# PSU.net
KiCad netlist of a schematic drawn in Altium Designer
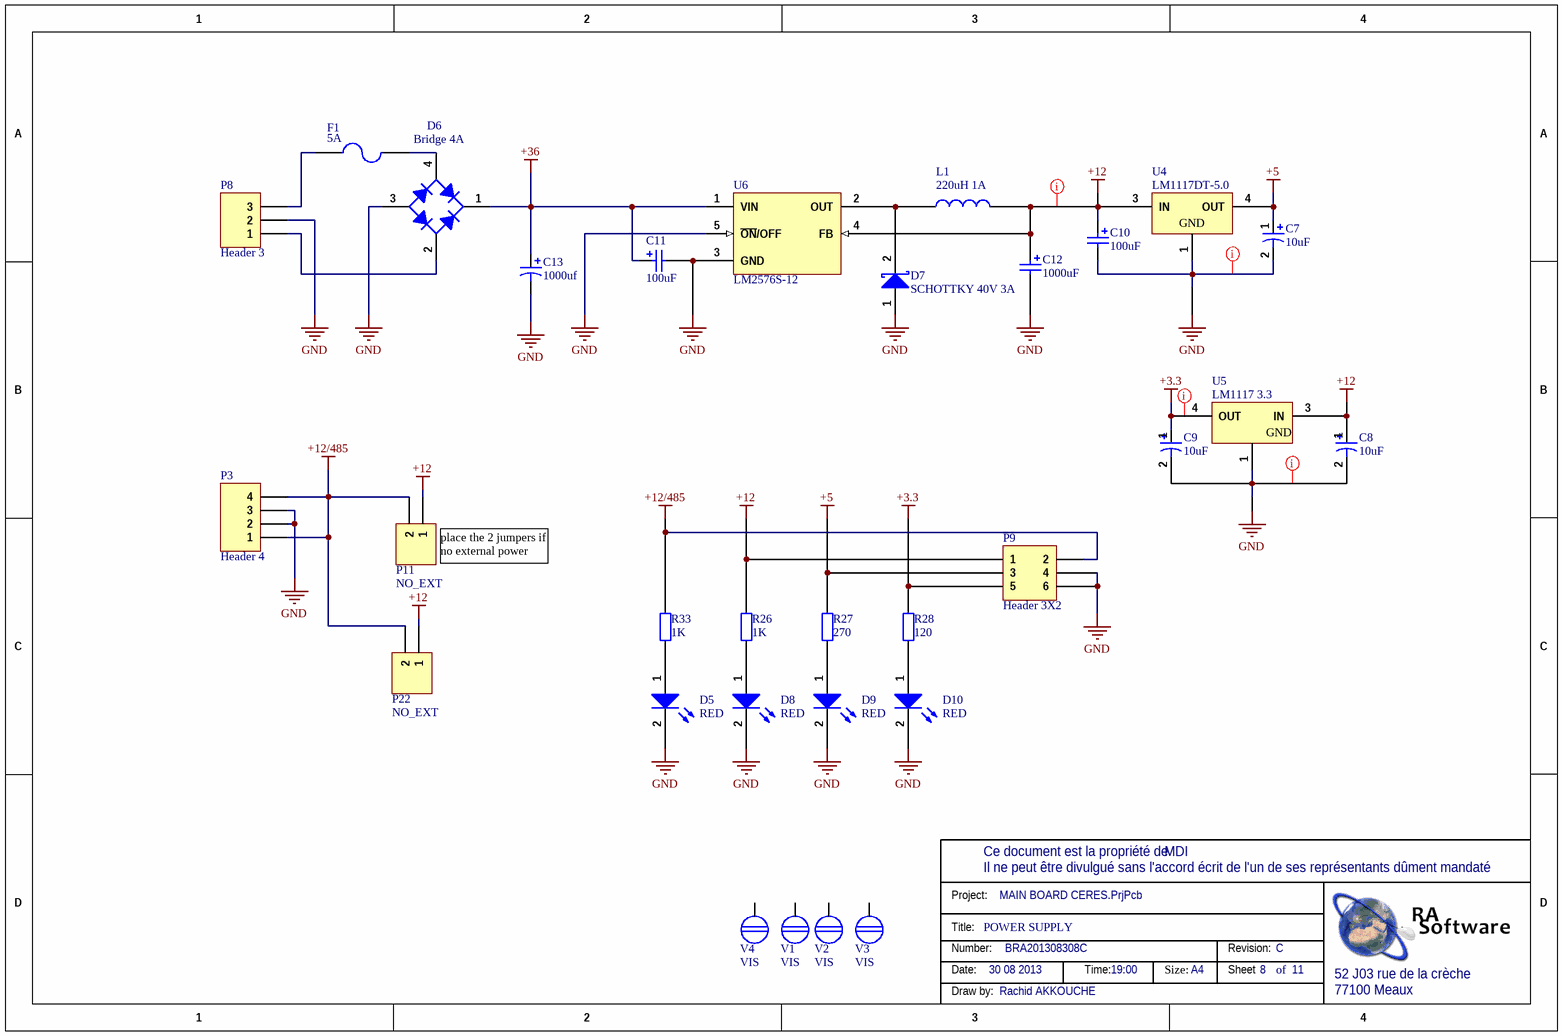
[diagram p0: PSU.SchDoc]

(export (version "E")
  (design (tool "Eeschema 10.0.6"))
  (components
    (comp (ref "C7")
      (value "10uF")
      (footprint "SYLANN:KEMET_4")
      (description "Polarized Capacitor")
      (fields
        (field (name "MANUFACTURER") "KEMET")
        (field (name "MANUFACTURER PART NUMBER") "EXV106M025A9BAA")
      )
      (libsource (lib "") (part "Cap Pol1_1"))
    )
    (comp (ref "C8")
      (value "10uF")
      (footprint "SYLANN:KEMET_4")
      (description "Polarized Capacitor")
      (fields
        (field (name "MANUFACTURER") "KEMET")
        (field (name "MANUFACTURER PART NUMBER") "EXV106M025A9BAA")
      )
      (libsource (lib "Miscellaneous Devices") (part "Cap Pol1"))
    )
    (comp (ref "C9")
      (value "10uF")
      (footprint "SYLANN:KEMET_4")
      (description "Polarized Capacitor")
      (fields
        (field (name "MANUFACTURER") "KEMET")
        (field (name "MANUFACTURER PART NUMBER") "EXV106M025A9BAA")
      )
      (libsource (lib "Miscellaneous Devices") (part "Cap Pol1"))
    )
    (comp (ref "C10")
      (value "100uF")
      (footprint "Kemet_63")
      (description "Polarized Capacitor")
      (fields
        (field (name "MANUFACTURER") "EPCOS")
        (field (name "MANUFACTURER PART NUMBER") "B41142A4107M")
        (field (name "HAUTEUR") "7.7")
        (field (name "LONGUEUR/HAUTEUR") "7.7")
      )
      (libsource (lib "BRA") (part "Cap Pol 100uF"))
    )
    (comp (ref "C11")
      (value "100uF")
      (footprint "Kemet_63")
      (description "Polarized Capacitor")
      (fields
        (field (name "MANUFACTURER") "EPCOS")
        (field (name "MANUFACTURER PART NUMBER") "B41142A4107M")
        (field (name "HAUTEUR") "7.7")
        (field (name "LONGUEUR/HAUTEUR") "7.7")
      )
      (libsource (lib "BRA") (part "Cap Pol 100uF"))
    )
    (comp (ref "C12")
      (value "1000uF")
      (footprint "KEMET_10")
      (description "Polarized Capacitor")
      (fields
        (field (name "MANUFACTURER") "PANASONIC")
        (field (name "MANUFACTURER PART NUMBER") "EEEFT1C102AP")
        (field (name "HAUTEUR") "10.2")
      )
      (libsource (lib "BRA") (part "Cap Pol 1000uF"))
    )
    (comp (ref "C13")
      (value "1000uf")
      (footprint "Capa Panasonic size J16")
      (description "Polarized Capacitor (Radial)")
      (fields
        (field (name "MANUFACTURER") "PANASONIC")
        (field (name "MANUFACTURER PART NUMBER") "EEVFK1H102M")
      )
      (libsource (lib "") (part "Cap Pol1_2"))
    )
    (comp (ref "D5")
      (value "HSMH-C190")
      (footprint "SYLANN:0603-LEDR")
      (description "Surface Mount Chip LED, Red")
      (fields
        (field (name "MANUFACTURER") "AVAGO TECHNOLOGIES")
        (field (name "MANUFACTURER PART NUMBER") "HSMH-C190.")
        (field (name "COULEUR") "RED")
        (field (name "LONGUEUR/HAUTEUR") "1.6")
      )
      (libsource (lib "Avago Optoelectronic LED") (part "HSMH-C190"))
    )
    (comp (ref "D6")
      (value "Bridge 4A")
      (footprint "Pont GBU")
      (description "Full Wave Diode Bridge")
      (fields
        (field (name "MANUFACTURER") "VISHAY GENERAL SEMICONDUCTOR")
        (field (name "MANUFACTURER PART NUMBER") "GBU6B-E3/45")
        (field (name "HAUTEUR") "18.8")
        (field (name "HAUTEUR CORPS MAX..") "18.8")
        (field (name "LONGUEUR/HAUTEUR") "18.8")
      )
      (libsource (lib "Miscellaneous Devices") (part "Bridge1"))
    )
    (comp (ref "D7")
      (value "SCHOTTKY 40V 3A")
      (footprint "DO220AA")
      (description "Schottky Diode")
      (fields
        (field (name "MANUFACTURER") "VISHAY")
        (field (name "MANUFACTURER PART NUMBER") "SS3P4-M3/84A")
        (field (name "PUBLISHER") "Altium Limited")
      )
      (libsource (lib "Miscellaneous Devices") (part "D Schottky"))
    )
    (comp (ref "D8")
      (value "HSMH-C190")
      (footprint "SYLANN:0603-LEDR")
      (description "Surface Mount Chip LED, Red")
      (fields
        (field (name "MANUFACTURER") "AVAGO TECHNOLOGIES")
        (field (name "MANUFACTURER PART NUMBER") "HSMH-C190.")
        (field (name "COULEUR") "RED")
        (field (name "LONGUEUR/HAUTEUR") "1.6")
      )
      (libsource (lib "Avago Optoelectronic LED") (part "HSMH-C190"))
    )
    (comp (ref "D9")
      (value "HSMH-C190")
      (footprint "SYLANN:0603-LEDR")
      (description "Surface Mount Chip LED, Red")
      (fields
        (field (name "MANUFACTURER") "AVAGO TECHNOLOGIES")
        (field (name "MANUFACTURER PART NUMBER") "HSMH-C190.")
        (field (name "COULEUR") "RED")
        (field (name "LONGUEUR/HAUTEUR") "1.6")
      )
      (libsource (lib "Avago Optoelectronic LED") (part "HSMH-C190"))
    )
    (comp (ref "D10")
      (value "HSMH-C190")
      (footprint "SYLANN:0603-LEDR")
      (description "Surface Mount Chip LED, Red")
      (fields
        (field (name "MANUFACTURER") "AVAGO TECHNOLOGIES")
        (field (name "MANUFACTURER PART NUMBER") "HSMH-C190.")
        (field (name "COULEUR") "RED")
        (field (name "LONGUEUR/HAUTEUR") "1.6")
      )
      (libsource (lib "Avago Optoelectronic LED") (part "HSMH-C190"))
    )
    (comp (ref "F1")
      (value "5A")
      (footprint "FUS5X20")
      (description "Fuse")
      (fields
        (field (name "MANUFACTURER") "KEYSTONE")
        (field (name "MANUFACTURER PART NUMBER") "4527")
        (field (name "PUBLISHER") "Altium Limited")
      )
      (libsource (lib "Miscellaneous Devices") (part "Fuse 2"))
    )
    (comp (ref "L1")
      (value "220uH 1A")
      (footprint "IND-1422435C")
      (description "Inductor")
      (fields
        (field (name "MANUFACTURER") "MULTICOMP")
        (field (name "MANUFACTURER PART NUMBER") "MCBFS7330-221MU")
        (field (name "LONGUEUR/HAUTEUR") "18.54")
      )
      (libsource (lib "Miscellaneous Devices") (part "Inductor"))
    )
    (comp (ref "P3")
      (value "Header 4")
      (footprint "CO4P508")
      (description "Header, 4-Pin")
      (fields (field (name "PUBLISHER") "Altium Limited"))
      (libsource (lib "Miscellaneous Connectors") (part "Header 4"))
    )
    (comp (ref "P8")
      (value "Header 3")
      (footprint "CO3P508")
      (description "Header, 3-Pin")
      (fields
        (field (name "MANUFACTURER") "TE CONNECTIVITY / BUCHANAN")
        (field (name "MANUFACTURER PART NUMBER") "796636-3")
        (field (name "PUBLISHER") "Altium Limited")
      )
      (libsource (lib "Miscellaneous Connectors") (part "Header 3"))
    )
    (comp (ref "P9")
      (value "Header 3X2")
      (footprint "M20-2X3")
      (description "Header, 3-Pin, Dual row")
      (fields
        (field (name "MANUFACTURER") "TE CONNECTIVITY / AMP")
        (field (name "MANUFACTURER PART NUMBER") "1241050-3")
        (field (name "PUBLISHER") "Altium Limited")
      )
      (libsource (lib "Miscellaneous Connectors") (part "Header 3X2"))
    )
    (comp (ref "P11")
      (value "NO_EXT")
      (footprint "M20_1X2")
      (description "Header, 2-Pin")
      (fields
        (field (name "MANUFACTURER") "HARWIN")
        (field (name "MANUFACTURER PART NUMBER") "M20-8770242")
        (field (name "PUBLISHER") "Altium Limited")
      )
      (libsource (lib "Miscellaneous Connectors") (part "Header 2"))
    )
    (comp (ref "P22")
      (value "NO_EXT")
      (footprint "M20_1X2")
      (description "Header, 2-Pin")
      (fields
        (field (name "MANUFACTURER") "HARWIN")
        (field (name "MANUFACTURER PART NUMBER") "M20-8770242")
        (field (name "PUBLISHER") "Altium Limited")
      )
      (libsource (lib "Miscellaneous Connectors") (part "Header 2"))
    )
    (comp (ref "R26")
      (value "1K")
      (footprint "R0805")
      (description "Resistor")
      (fields
        (field (name "MANUFACTURER") "MULTICOMP")
        (field (name "MANUFACTURER PART NUMBER") "MC0.1W08051%1KFR")
      )
      (libsource (lib "BRA") (part "Resistor 0805 1K"))
    )
    (comp (ref "R27")
      (value "270")
      (footprint "R0805")
      (description "Resistor")
      (fields
        (field (name "MANUFACTURER") "MULTICOMP")
        (field (name "MANUFACTURER PART NUMBER") "MC01W08051270R")
      )
      (libsource (lib "BRA") (part "Resistor 0805 270"))
    )
    (comp (ref "R28")
      (value "120")
      (footprint "R0805")
      (description "Resistor")
      (fields
        (field (name "MANUFACTURER") "MULTICOMP")
        (field (name "MANUFACTURER PART NUMBER") "MC0.1W08051%1KFR")
      )
      (libsource (lib "BRA") (part "Resistor 0805 1K"))
    )
    (comp (ref "R33")
      (value "1K")
      (footprint "R0805")
      (description "Resistor")
      (fields
        (field (name "MANUFACTURER") "MULTICOMP")
        (field (name "MANUFACTURER PART NUMBER") "MC0.1W08051%1KFR")
      )
      (libsource (lib "BRA") (part "Resistor 0805 1K"))
    )
    (comp (ref "U4")
      (value "LM1117DT-5.0")
      (footprint "SOT223")
      (description "800mA Low-Dropout Linear Regulator, 3-pin TO-252")
      (fields (field (name "MANUFACTURER") "NXP") (field (name "MANUFACTURER PART NUMBER") "NX1117C50Z"))
      (libsource (lib "NSC LDO") (part "LM1117DT-5.0"))
    )
    (comp (ref "U5")
      (value "LM1117 3.3")
      (footprint "TO252")
      (description "800mA Low-Dropout Linear Regulator, 3-pin TO-252")
      (fields
        (field (name "MANUFACTURER") "DIODES INC.")
        (field (name "MANUFACTURER PART NUMBER") "AP1117D33G-13")
      )
      (libsource (lib "Interface Lavazza blue") (part "LM1117DT-3.3"))
    )
    (comp (ref "U6")
      (value "LM2576S-12")
      (footprint "TO263-5")
      (description "SIMPLE SWITCHER® 3A Step-Down Voltage Regulator, 5-pin TO-220")
      (fields
        (field (name "MANUFACTURER") "TEXAS INSTRUMENTS")
        (field (name "MANUFACTURER PART NUMBER") "LM2576HVS-12/NOPB")
      )
      (libsource (lib "NSC Switcher") (part "LM2576HVT-12"))
    )
    (comp (ref "V1") (value "VIS") (footprint "VIS42") (libsource (lib "UTIL_Library") (part "VIS")))
    (comp (ref "V2") (value "VIS") (footprint "VIS42") (libsource (lib "UTIL_Library") (part "VIS")))
    (comp (ref "V3") (value "VIS") (footprint "VIS42") (libsource (lib "UTIL_Library") (part "VIS")))
    (comp (ref "V4") (value "VIS") (footprint "VIS42") (libsource (lib "UTIL_Library") (part "VIS")))
  )
  (nets
    (net (code "1") (name "+3.3") (class "Default")
      (node (ref "C9") (pin "1") (pinfunction "1_1") (pintype "passive"))
      (node (ref "P9") (pin "5") (pinfunction "5_5") (pintype "passive"))
      (node (ref "R28") (pin "2") (pinfunction "2_2") (pintype "passive"))
      (node (ref "U5") (pin "4") (pinfunction "OUT_4") (pintype "power_in"))
    )
    (net (code "2") (name "+5") (class "Default")
      (node (ref "C7") (pin "1") (pinfunction "1_1") (pintype "passive"))
      (node (ref "P9") (pin "3") (pinfunction "3_3") (pintype "passive"))
      (node (ref "R27") (pin "2") (pinfunction "2_2") (pintype "passive"))
      (node (ref "U4") (pin "4") (pinfunction "OUT_4") (pintype "power_in"))
    )
    (net (code "3") (name "+12") (class "Default")
      (node (ref "C10") (pin "1") (pinfunction "1_1") (pintype "passive"))
      (node (ref "C12") (pin "1") (pinfunction "1_1") (pintype "passive"))
      (node (ref "C8") (pin "1") (pinfunction "1_1") (pintype "passive"))
      (node (ref "L1") (pin "2") (pinfunction "2_2") (pintype "passive"))
      (node (ref "P11") (pin "1") (pinfunction "1_1") (pintype "passive"))
      (node (ref "P22") (pin "1") (pinfunction "1_1") (pintype "passive"))
      (node (ref "P9") (pin "1") (pinfunction "1_1") (pintype "passive"))
      (node (ref "R26") (pin "2") (pinfunction "2_2") (pintype "passive"))
      (node (ref "U4") (pin "3") (pinfunction "IN_3") (pintype "power_in"))
      (node (ref "U5") (pin "3") (pinfunction "IN_3") (pintype "power_in"))
      (node (ref "U6") (pin "4") (pinfunction "FB_4") (pintype "input"))
    )
    (net (code "4") (name "+12{slash}485") (class "Default")
      (node (ref "P11") (pin "2") (pinfunction "2_2") (pintype "passive"))
      (node (ref "P22") (pin "2") (pinfunction "2_2") (pintype "passive"))
      (node (ref "P3") (pin "1") (pinfunction "1_1") (pintype "passive"))
      (node (ref "P3") (pin "4") (pinfunction "4_4") (pintype "passive"))
      (node (ref "P9") (pin "2") (pinfunction "2_2") (pintype "passive"))
      (node (ref "R33") (pin "2") (pinfunction "2_2") (pintype "passive"))
    )
    (net (code "5") (name "+36") (class "Default")
      (node (ref "C11") (pin "1") (pinfunction "1_1") (pintype "passive"))
      (node (ref "C13") (pin "1") (pinfunction "1_1") (pintype "passive"))
      (node (ref "D6") (pin "1") (pinfunction "K_1") (pintype "passive"))
      (node (ref "U6") (pin "1") (pinfunction "VIN_1") (pintype "power_in"))
    )
    (net (code "6") (name "GND") (class "Default")
      (node (ref "C10") (pin "2") (pinfunction "2_2") (pintype "passive"))
      (node (ref "C11") (pin "2") (pinfunction "2_2") (pintype "passive"))
      (node (ref "C12") (pin "2") (pinfunction "2_2") (pintype "passive"))
      (node (ref "C13") (pin "2") (pinfunction "2_2") (pintype "passive"))
      (node (ref "C7") (pin "2") (pinfunction "2_2") (pintype "passive"))
      (node (ref "C8") (pin "2") (pinfunction "2_2") (pintype "passive"))
      (node (ref "C9") (pin "2") (pinfunction "2_2") (pintype "passive"))
      (node (ref "D10") (pin "2") (pinfunction "K_2") (pintype "passive"))
      (node (ref "D5") (pin "2") (pinfunction "K_2") (pintype "passive"))
      (node (ref "D6") (pin "3") (pinfunction "A_3") (pintype "passive"))
      (node (ref "D7") (pin "1") (pinfunction "A_1") (pintype "passive"))
      (node (ref "D8") (pin "2") (pinfunction "K_2") (pintype "passive"))
      (node (ref "D9") (pin "2") (pinfunction "K_2") (pintype "passive"))
      (node (ref "P3") (pin "2") (pinfunction "2_2") (pintype "passive"))
      (node (ref "P3") (pin "3") (pinfunction "3_3") (pintype "passive"))
      (node (ref "P8") (pin "2") (pinfunction "2_2") (pintype "passive"))
      (node (ref "P9") (pin "4") (pinfunction "4_4") (pintype "passive"))
      (node (ref "P9") (pin "6") (pinfunction "6_6") (pintype "passive"))
      (node (ref "U4") (pin "1") (pinfunction "GND_1") (pintype "power_in"))
      (node (ref "U5") (pin "1") (pinfunction "GND_1") (pintype "power_in"))
      (node (ref "U6") (pin "3") (pinfunction "GND_3") (pintype "power_in"))
      (node (ref "U6") (pin "5") (pinfunction "~{ON}/OFF_5") (pintype "input"))
    )
    (net (code "7") (name "Net-(D5-A)") (class "Default")
      (node (ref "D5") (pin "1") (pinfunction "A_1") (pintype "passive"))
      (node (ref "R33") (pin "1") (pinfunction "1_1") (pintype "passive"))
    )
    (net (code "8") (name "Net-(D6-C-Pad2)") (class "Default")
      (node (ref "D6") (pin "2") (pinfunction "C_2") (pintype "passive"))
      (node (ref "P8") (pin "1") (pinfunction "1_1") (pintype "passive"))
    )
    (net (code "9") (name "Net-(D6-C-Pad4)") (class "Default")
      (node (ref "D6") (pin "4") (pinfunction "C_4") (pintype "passive"))
      (node (ref "F1") (pin "2") (pinfunction "2_2") (pintype "passive"))
    )
    (net (code "10") (name "Net-(D7-K)") (class "Default")
      (node (ref "D7") (pin "2") (pinfunction "K_2") (pintype "passive"))
      (node (ref "L1") (pin "1") (pinfunction "1_1") (pintype "passive"))
      (node (ref "U6") (pin "2") (pinfunction "OUT_2") (pintype "power_in"))
    )
    (net (code "11") (name "Net-(D8-A)") (class "Default")
      (node (ref "D8") (pin "1") (pinfunction "A_1") (pintype "passive"))
      (node (ref "R26") (pin "1") (pinfunction "1_1") (pintype "passive"))
    )
    (net (code "12") (name "Net-(D9-A)") (class "Default")
      (node (ref "D9") (pin "1") (pinfunction "A_1") (pintype "passive"))
      (node (ref "R27") (pin "1") (pinfunction "1_1") (pintype "passive"))
    )
    (net (code "13") (name "Net-(D10-A)") (class "Default")
      (node (ref "D10") (pin "1") (pinfunction "A_1") (pintype "passive"))
      (node (ref "R28") (pin "1") (pinfunction "1_1") (pintype "passive"))
    )
    (net (code "14") (name "Net-(F1-Pad1)") (class "Default")
      (node (ref "F1") (pin "1") (pinfunction "1_1") (pintype "passive"))
      (node (ref "P8") (pin "3") (pinfunction "3_3") (pintype "passive"))
    )
    (net (code "15") (name "unconnected-(V1-Pad1)") (class "Default")
      (node (ref "V1") (pin "1") (pinfunction "1_1") (pintype "passive"))
    )
    (net (code "16") (name "unconnected-(V2-Pad1)") (class "Default")
      (node (ref "V2") (pin "1") (pinfunction "1_1") (pintype "passive"))
    )
    (net (code "17") (name "unconnected-(V3-Pad1)") (class "Default")
      (node (ref "V3") (pin "1") (pinfunction "1_1") (pintype "passive"))
    )
    (net (code "18") (name "unconnected-(V4-Pad1)") (class "Default")
      (node (ref "V4") (pin "1") (pinfunction "1_1") (pintype "passive"))
    )
  )
)
